# plant_long_life_v1_20.net
KiCad netlist of a schematic drawn in EAGLE
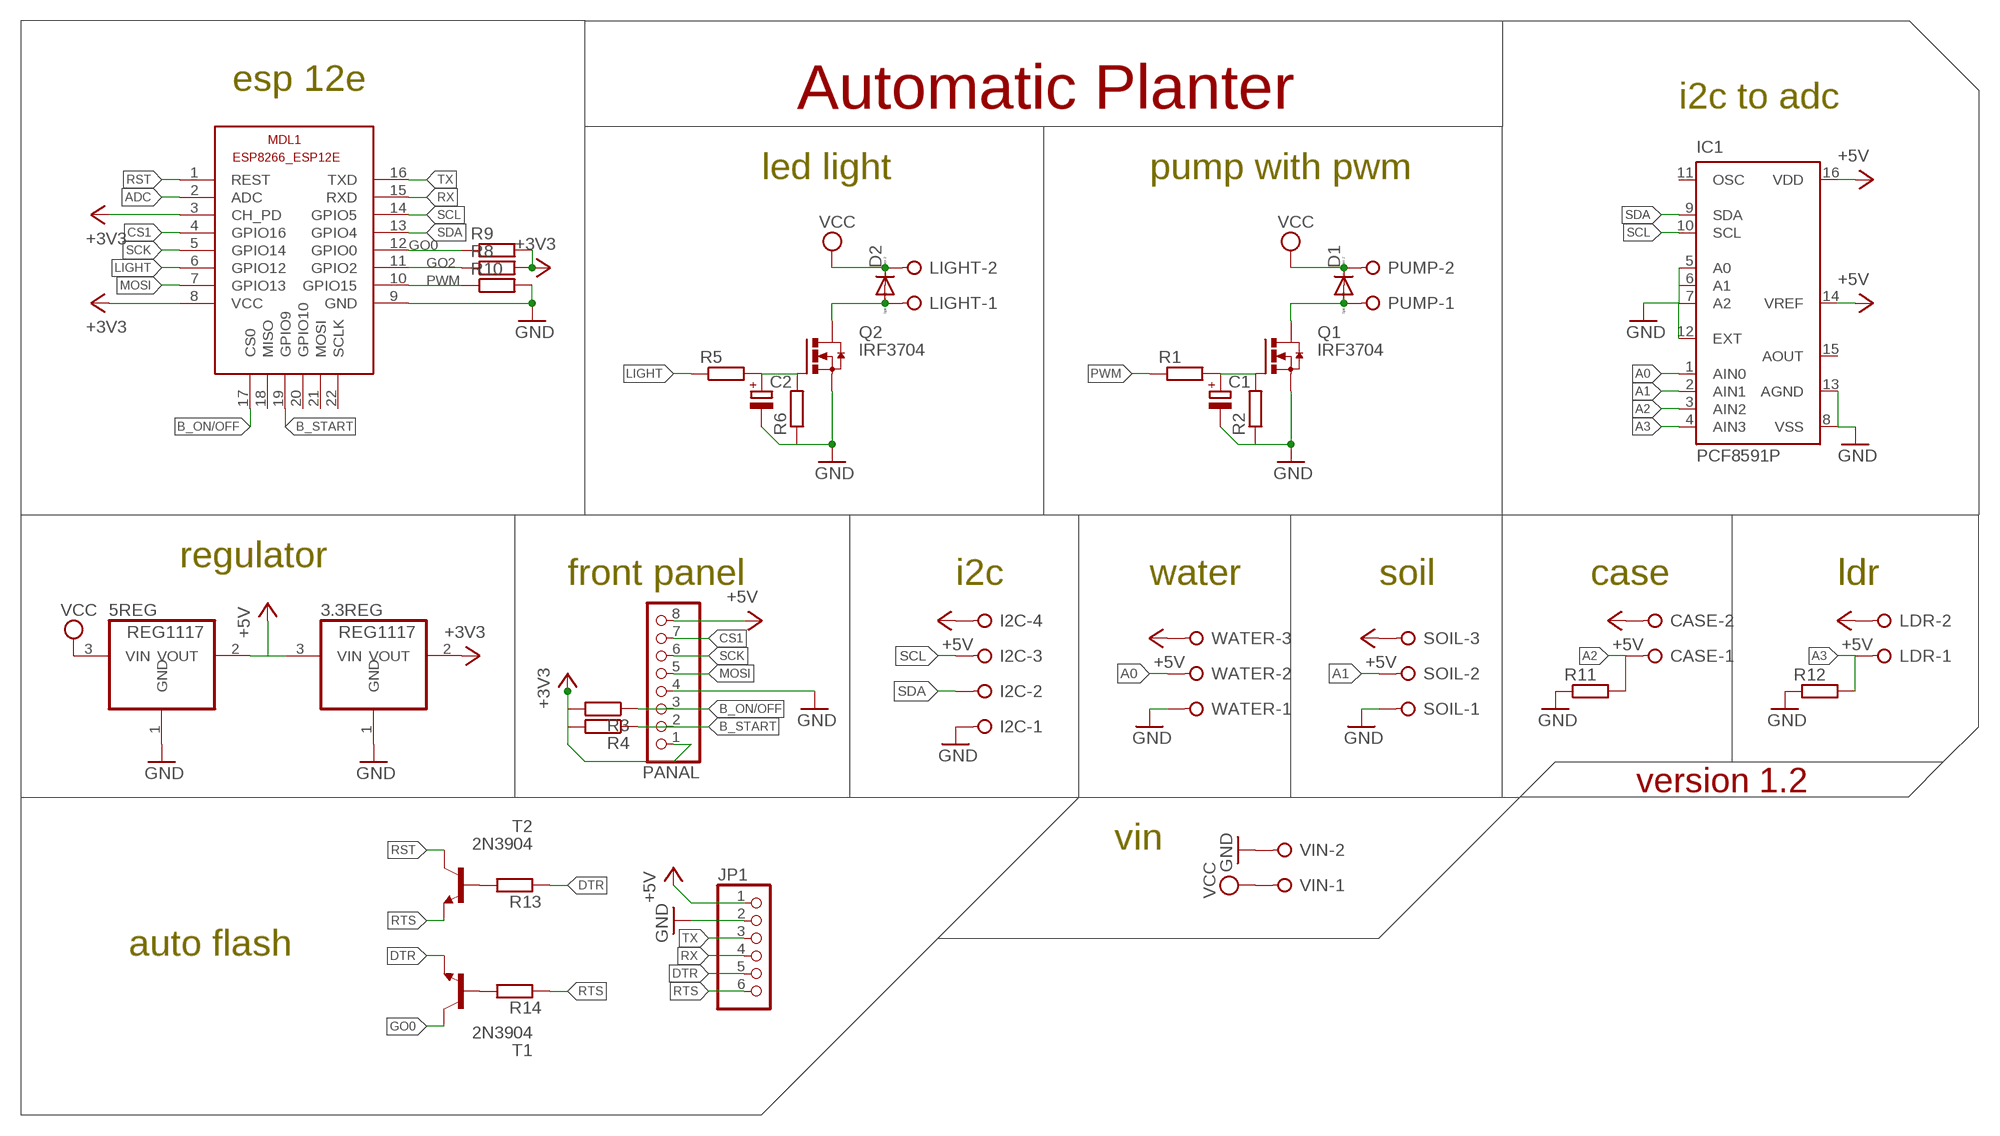
[diagram p0: schematic, sheet 1]

(export (version "E")
  (design (tool "Eeschema 10.0.6"))
  (components
    (comp (ref "3.3REG")
      (value "REG1117")
      (footprint "eagle-import:SOT223")
      (libsource (lib "eagle-import") (part "REG1117"))
    )
    (comp (ref "5REG")
      (value "REG1117")
      (footprint "eagle-import:SOT223")
      (libsource (lib "eagle-import") (part "REG1117"))
    )
    (comp (ref "C1")
      (value "CPOL-EUSMCA")
      (footprint "eagle-import:SMC_A")
      (libsource (lib "eagle-import") (part "CPOL-EUSMCA"))
    )
    (comp (ref "C2")
      (value "CPOL-EUSMCA")
      (footprint "eagle-import:SMC_A")
      (libsource (lib "eagle-import") (part "CPOL-EUSMCA"))
    )
    (comp (ref "CASE")
      (value "W237-02P")
      (footprint "eagle-import:W237-132")
      (libsource (lib "eagle-import") (part "W237-02P"))
    )
    (comp (ref "D1")
      (value "DIODE-DO214AA")
      (footprint "eagle-import:DO214AA")
      (libsource (lib "eagle-import") (part "DIODE-DO214AA"))
    )
    (comp (ref "D2")
      (value "DIODE-DO214AA")
      (footprint "eagle-import:DO214AA")
      (libsource (lib "eagle-import") (part "DIODE-DO214AA"))
    )
    (comp (ref "I2C")
      (value "W237-04P")
      (footprint "eagle-import:W237-4P")
      (libsource (lib "eagle-import") (part "W237-04P"))
    )
    (comp (ref "IC1")
      (value "PCF8591P")
      (footprint "eagle-import:DIL16")
      (fields (field (name "MF") "FARNELL"))
      (libsource (lib "eagle-import") (part "PCF8591P"))
    )
    (comp (ref "JP1")
      (value "PINHD-1X6")
      (footprint "eagle-import:1X06")
      (libsource (lib "eagle-import") (part "PINHD-1X6"))
    )
    (comp (ref "LDR")
      (value "W237-02P")
      (footprint "eagle-import:W237-132")
      (libsource (lib "eagle-import") (part "W237-02P"))
    )
    (comp (ref "LIGHT")
      (value "W237-02P")
      (footprint "eagle-import:W237-132")
      (libsource (lib "eagle-import") (part "W237-02P"))
    )
    (comp (ref "MDL1")
      (value "ESP8266-12EESP8266-ESP12E")
      (footprint "eagle-import:ESP8266-ESP12E")
      (libsource (lib "eagle-import") (part "ESP8266-12EESP8266-ESP12E"))
    )
    (comp (ref "PANAL")
      (value "PINHD-1X8")
      (footprint "eagle-import:1X08")
      (libsource (lib "eagle-import") (part "PINHD-1X8"))
    )
    (comp (ref "PUMP")
      (value "W237-02P")
      (footprint "eagle-import:W237-132")
      (libsource (lib "eagle-import") (part "W237-02P"))
    )
    (comp (ref "Q1")
      (value "IRF3704")
      (footprint "eagle-import:TO220AH")
      (libsource (lib "eagle-import") (part "IRF3704"))
    )
    (comp (ref "Q2")
      (value "IRF3704")
      (footprint "eagle-import:TO220AH")
      (libsource (lib "eagle-import") (part "IRF3704"))
    )
    (comp (ref "R1")
      (value "R-EU_R0805")
      (footprint "eagle-import:R0805")
      (libsource (lib "eagle-import") (part "R-EU_R0805"))
    )
    (comp (ref "R2")
      (value "R-EU_R0805")
      (footprint "eagle-import:R0805")
      (libsource (lib "eagle-import") (part "R-EU_R0805"))
    )
    (comp (ref "R3")
      (value "R-EU_R0805")
      (footprint "eagle-import:R0805")
      (libsource (lib "eagle-import") (part "R-EU_R0805"))
    )
    (comp (ref "R4")
      (value "R-EU_R0805")
      (footprint "eagle-import:R0805")
      (libsource (lib "eagle-import") (part "R-EU_R0805"))
    )
    (comp (ref "R5")
      (value "R-EU_R0805")
      (footprint "eagle-import:R0805")
      (libsource (lib "eagle-import") (part "R-EU_R0805"))
    )
    (comp (ref "R6")
      (value "R-EU_R0805")
      (footprint "eagle-import:R0805")
      (libsource (lib "eagle-import") (part "R-EU_R0805"))
    )
    (comp (ref "R8")
      (value "R-EU_R0603")
      (footprint "eagle-import:R0603")
      (libsource (lib "eagle-import") (part "R-EU_R0603"))
    )
    (comp (ref "R9")
      (value "R-EU_R0603")
      (footprint "eagle-import:R0603")
      (libsource (lib "eagle-import") (part "R-EU_R0603"))
    )
    (comp (ref "R10")
      (value "R-EU_R0603")
      (footprint "eagle-import:R0603")
      (libsource (lib "eagle-import") (part "R-EU_R0603"))
    )
    (comp (ref "R11")
      (value "R-EU_R0805")
      (footprint "eagle-import:R0805")
      (libsource (lib "eagle-import") (part "R-EU_R0805"))
    )
    (comp (ref "R12")
      (value "R-EU_R0805")
      (footprint "eagle-import:R0805")
      (libsource (lib "eagle-import") (part "R-EU_R0805"))
    )
    (comp (ref "R13")
      (value "R-EU_0204/7")
      (footprint "eagle-import:0204_7")
      (libsource (lib "eagle-import") (part "R-EU_0204/7"))
    )
    (comp (ref "R14")
      (value "R-EU_0204/7")
      (footprint "eagle-import:0204_7")
      (libsource (lib "eagle-import") (part "R-EU_0204/7"))
    )
    (comp (ref "SOIL")
      (value "W237-3E")
      (footprint "eagle-import:W237-3E")
      (libsource (lib "eagle-import") (part "W237-3E"))
    )
    (comp (ref "T1")
      (value "2N3904")
      (footprint "eagle-import:TO92")
      (libsource (lib "eagle-import") (part "2N3904"))
    )
    (comp (ref "T2")
      (value "2N3904")
      (footprint "eagle-import:TO92")
      (libsource (lib "eagle-import") (part "2N3904"))
    )
    (comp (ref "VIN")
      (value "W237-02P")
      (footprint "eagle-import:W237-132")
      (libsource (lib "eagle-import") (part "W237-02P"))
    )
    (comp (ref "WATER")
      (value "W237-3E")
      (footprint "eagle-import:W237-3E")
      (libsource (lib "eagle-import") (part "W237-3E"))
    )
  )
  (nets
    (net (code "1") (name "+3V3") (class "Default")
      (node (ref "3.3REG") (pin "2") (pinfunction "VOUT_2") (pintype "output"))
      (node (ref "MDL1") (pin "3") (pinfunction "CH_PD_3") (pintype "bidirectional"))
      (node (ref "MDL1") (pin "8") (pinfunction "VCC_8") (pintype "bidirectional"))
      (node (ref "PANAL") (pin "1") (pinfunction "1_1") (pintype "passive"))
      (node (ref "R3") (pin "2") (pinfunction "2_2") (pintype "passive"))
      (node (ref "R4") (pin "2") (pinfunction "2_2") (pintype "passive"))
      (node (ref "R8") (pin "2") (pinfunction "2_2") (pintype "passive"))
      (node (ref "R9") (pin "2") (pinfunction "2_2") (pintype "passive"))
    )
    (net (code "2") (name "+5V") (class "Default")
      (node (ref "3.3REG") (pin "3") (pinfunction "VIN_3") (pintype "input"))
      (node (ref "5REG") (pin "2") (pinfunction "VOUT_2") (pintype "output"))
      (node (ref "CASE") (pin "2") (pinfunction "KL_2") (pintype "passive"))
      (node (ref "I2C") (pin "4") (pinfunction "KL_4") (pintype "passive"))
      (node (ref "IC1") (pin "14") (pinfunction "VREF_14") (pintype "input"))
      (node (ref "IC1") (pin "16") (pinfunction "VDD_16") (pintype "power_in"))
      (node (ref "JP1") (pin "1") (pinfunction "1_1") (pintype "passive"))
      (node (ref "LDR") (pin "2") (pinfunction "KL_2") (pintype "passive"))
      (node (ref "PANAL") (pin "8") (pinfunction "8_8") (pintype "passive"))
      (node (ref "SOIL") (pin "3") (pinfunction "KL_3") (pintype "passive"))
      (node (ref "WATER") (pin "3") (pinfunction "KL_3") (pintype "passive"))
    )
    (net (code "3") (name "/GO2") (class "Default")
      (node (ref "MDL1") (pin "11") (pinfunction "GPIO2_11") (pintype "bidirectional"))
      (node (ref "R8") (pin "1") (pinfunction "1_1") (pintype "passive"))
    )
    (net (code "4") (name "A0") (class "Default")
      (node (ref "IC1") (pin "1") (pinfunction "AIN0_1") (pintype "input"))
      (node (ref "WATER") (pin "2") (pinfunction "KL_2") (pintype "passive"))
    )
    (net (code "5") (name "A1") (class "Default")
      (node (ref "IC1") (pin "2") (pinfunction "AIN1_2") (pintype "input"))
      (node (ref "SOIL") (pin "2") (pinfunction "KL_2") (pintype "passive"))
    )
    (net (code "6") (name "A2") (class "Default")
      (node (ref "CASE") (pin "1") (pinfunction "KL_1") (pintype "passive"))
      (node (ref "IC1") (pin "3") (pinfunction "AIN2_3") (pintype "input"))
      (node (ref "R11") (pin "2") (pinfunction "2_2") (pintype "passive"))
    )
    (net (code "7") (name "A3") (class "Default")
      (node (ref "IC1") (pin "4") (pinfunction "AIN3_4") (pintype "input"))
      (node (ref "LDR") (pin "1") (pinfunction "KL_1") (pintype "passive"))
      (node (ref "R12") (pin "2") (pinfunction "2_2") (pintype "passive"))
    )
    (net (code "8") (name "ADC") (class "Default")
      (node (ref "MDL1") (pin "2") (pinfunction "ADC_2") (pintype "bidirectional"))
    )
    (net (code "9") (name "B_ON{slash}OFF") (class "Default")
      (node (ref "MDL1") (pin "17") (pinfunction "CS0_17") (pintype "bidirectional"))
      (node (ref "PANAL") (pin "3") (pinfunction "3_3") (pintype "passive"))
      (node (ref "R3") (pin "1") (pinfunction "1_1") (pintype "passive"))
    )
    (net (code "10") (name "B_START") (class "Default")
      (node (ref "MDL1") (pin "19") (pinfunction "GPIO9_19") (pintype "bidirectional"))
      (node (ref "PANAL") (pin "2") (pinfunction "2_2") (pintype "passive"))
      (node (ref "R4") (pin "1") (pinfunction "1_1") (pintype "passive"))
    )
    (net (code "11") (name "CS1") (class "Default")
      (node (ref "MDL1") (pin "4") (pinfunction "GPIO16_4") (pintype "bidirectional"))
      (node (ref "PANAL") (pin "7") (pinfunction "7_7") (pintype "passive"))
    )
    (net (code "12") (name "DTR") (class "Default")
      (node (ref "JP1") (pin "5") (pinfunction "5_5") (pintype "passive"))
      (node (ref "R13") (pin "1") (pinfunction "1_1") (pintype "passive"))
      (node (ref "T1") (pin "3") (pinfunction "E_3") (pintype "passive"))
    )
    (net (code "13") (name "GND") (class "Default")
      (node (ref "3.3REG") (pin "1") (pinfunction "GND_1") (pintype "power_in"))
      (node (ref "5REG") (pin "1") (pinfunction "GND_1") (pintype "power_in"))
      (node (ref "C1") (pin "-") (pinfunction "-_-") (pintype "passive"))
      (node (ref "C2") (pin "-") (pinfunction "-_-") (pintype "passive"))
      (node (ref "I2C") (pin "1") (pinfunction "KL_1") (pintype "passive"))
      (node (ref "IC1") (pin "12") (pinfunction "EXT_12") (pintype "input"))
      (node (ref "IC1") (pin "13") (pinfunction "AGND_13") (pintype "power_in"))
      (node (ref "IC1") (pin "5") (pinfunction "A0_5") (pintype "input"))
      (node (ref "IC1") (pin "6") (pinfunction "A1_6") (pintype "input"))
      (node (ref "IC1") (pin "7") (pinfunction "A2_7") (pintype "input"))
      (node (ref "IC1") (pin "8") (pinfunction "VSS_8") (pintype "power_in"))
      (node (ref "JP1") (pin "2") (pinfunction "2_2") (pintype "passive"))
      (node (ref "MDL1") (pin "9") (pinfunction "GND_9") (pintype "bidirectional"))
      (node (ref "PANAL") (pin "4") (pinfunction "4_4") (pintype "passive"))
      (node (ref "Q1") (pin "E") (pinfunction "S_E") (pintype "passive"))
      (node (ref "Q2") (pin "E") (pinfunction "S_E") (pintype "passive"))
      (node (ref "R10") (pin "2") (pinfunction "2_2") (pintype "passive"))
      (node (ref "R11") (pin "1") (pinfunction "1_1") (pintype "passive"))
      (node (ref "R12") (pin "1") (pinfunction "1_1") (pintype "passive"))
      (node (ref "R2") (pin "1") (pinfunction "1_1") (pintype "passive"))
      (node (ref "R6") (pin "1") (pinfunction "1_1") (pintype "passive"))
      (node (ref "SOIL") (pin "1") (pinfunction "KL_1") (pintype "passive"))
      (node (ref "VIN") (pin "2") (pinfunction "KL_2") (pintype "passive"))
      (node (ref "WATER") (pin "1") (pinfunction "KL_1") (pintype "passive"))
    )
    (net (code "14") (name "GO0") (class "Default")
      (node (ref "MDL1") (pin "12") (pinfunction "GPIO0_12") (pintype "bidirectional"))
      (node (ref "R9") (pin "1") (pinfunction "1_1") (pintype "passive"))
      (node (ref "T1") (pin "1") (pinfunction "C_1") (pintype "passive"))
    )
    (net (code "15") (name "LIGHT") (class "Default")
      (node (ref "MDL1") (pin "6") (pinfunction "GPIO12_6") (pintype "bidirectional"))
      (node (ref "R5") (pin "1") (pinfunction "1_1") (pintype "passive"))
    )
    (net (code "16") (name "MOSI") (class "Default")
      (node (ref "MDL1") (pin "7") (pinfunction "GPIO13_7") (pintype "bidirectional"))
      (node (ref "PANAL") (pin "5") (pinfunction "5_5") (pintype "passive"))
    )
    (net (code "17") (name "Net-(LIGHTA-KL)") (class "Default")
      (node (ref "D2") (pin "A") (pinfunction "A_A") (pintype "passive"))
      (node (ref "LIGHT") (pin "1") (pinfunction "KL_1") (pintype "passive"))
      (node (ref "Q2") (pin "C") (pinfunction "D_C") (pintype "passive"))
    )
    (net (code "18") (name "Net-(PUMPA-KL)") (class "Default")
      (node (ref "D1") (pin "A") (pinfunction "A_A") (pintype "passive"))
      (node (ref "PUMP") (pin "1") (pinfunction "KL_1") (pintype "passive"))
      (node (ref "Q1") (pin "C") (pinfunction "D_C") (pintype "passive"))
    )
    (net (code "19") (name "Net-(Q1-G)") (class "Default")
      (node (ref "C1") (pin "+") (pinfunction "+_+") (pintype "passive"))
      (node (ref "Q1") (pin "B") (pinfunction "G_B") (pintype "passive"))
      (node (ref "R1") (pin "2") (pinfunction "2_2") (pintype "passive"))
      (node (ref "R2") (pin "2") (pinfunction "2_2") (pintype "passive"))
    )
    (net (code "20") (name "Net-(Q2-G)") (class "Default")
      (node (ref "C2") (pin "+") (pinfunction "+_+") (pintype "passive"))
      (node (ref "Q2") (pin "B") (pinfunction "G_B") (pintype "passive"))
      (node (ref "R5") (pin "2") (pinfunction "2_2") (pintype "passive"))
      (node (ref "R6") (pin "2") (pinfunction "2_2") (pintype "passive"))
    )
    (net (code "21") (name "Net-(T1-B)") (class "Default")
      (node (ref "R14") (pin "2") (pinfunction "2_2") (pintype "passive"))
      (node (ref "T1") (pin "2") (pinfunction "B_2") (pintype "passive"))
    )
    (net (code "22") (name "Net-(T2-B)") (class "Default")
      (node (ref "R13") (pin "2") (pinfunction "2_2") (pintype "passive"))
      (node (ref "T2") (pin "2") (pinfunction "B_2") (pintype "passive"))
    )
    (net (code "23") (name "PWM") (class "Default")
      (node (ref "MDL1") (pin "10") (pinfunction "GPIO15_10") (pintype "bidirectional"))
      (node (ref "R1") (pin "1") (pinfunction "1_1") (pintype "passive"))
      (node (ref "R10") (pin "1") (pinfunction "1_1") (pintype "passive"))
    )
    (net (code "24") (name "RST") (class "Default")
      (node (ref "MDL1") (pin "1") (pinfunction "REST_1") (pintype "bidirectional"))
      (node (ref "T2") (pin "1") (pinfunction "C_1") (pintype "passive"))
    )
    (net (code "25") (name "RTS") (class "Default")
      (node (ref "JP1") (pin "6") (pinfunction "6_6") (pintype "passive"))
      (node (ref "R14") (pin "1") (pinfunction "1_1") (pintype "passive"))
      (node (ref "T2") (pin "3") (pinfunction "E_3") (pintype "passive"))
    )
    (net (code "26") (name "RX") (class "Default")
      (node (ref "JP1") (pin "4") (pinfunction "4_4") (pintype "passive"))
      (node (ref "MDL1") (pin "15") (pinfunction "RXD_15") (pintype "bidirectional"))
    )
    (net (code "27") (name "SCK") (class "Default")
      (node (ref "MDL1") (pin "5") (pinfunction "GPIO14_5") (pintype "bidirectional"))
      (node (ref "PANAL") (pin "6") (pinfunction "6_6") (pintype "passive"))
    )
    (net (code "28") (name "SCL") (class "Default")
      (node (ref "I2C") (pin "3") (pinfunction "KL_3") (pintype "passive"))
      (node (ref "IC1") (pin "10") (pinfunction "SCL_10") (pintype "input"))
      (node (ref "MDL1") (pin "14") (pinfunction "GPIO5_14") (pintype "bidirectional"))
    )
    (net (code "29") (name "SDA") (class "Default")
      (node (ref "I2C") (pin "2") (pinfunction "KL_2") (pintype "passive"))
      (node (ref "IC1") (pin "9") (pinfunction "SDA_9") (pintype "bidirectional"))
      (node (ref "MDL1") (pin "13") (pinfunction "GPIO4_13") (pintype "bidirectional"))
    )
    (net (code "30") (name "TX") (class "Default")
      (node (ref "JP1") (pin "3") (pinfunction "3_3") (pintype "passive"))
      (node (ref "MDL1") (pin "16") (pinfunction "TXD_16") (pintype "bidirectional"))
    )
    (net (code "31") (name "VCC") (class "Default")
      (node (ref "5REG") (pin "3") (pinfunction "VIN_3") (pintype "input"))
      (node (ref "D1") (pin "C") (pinfunction "C_C") (pintype "passive"))
      (node (ref "D2") (pin "C") (pinfunction "C_C") (pintype "passive"))
      (node (ref "LIGHT") (pin "2") (pinfunction "KL_2") (pintype "passive"))
      (node (ref "PUMP") (pin "2") (pinfunction "KL_2") (pintype "passive"))
      (node (ref "VIN") (pin "1") (pinfunction "KL_1") (pintype "passive"))
    )
    (net (code "32") (name "unconnected-(IC1-AOUT-Pad15)") (class "Default")
      (node (ref "IC1") (pin "15") (pinfunction "AOUT_15") (pintype "output"))
    )
    (net (code "33") (name "unconnected-(IC1-OSC-Pad11)") (class "Default")
      (node (ref "IC1") (pin "11") (pinfunction "OSC_11") (pintype "input"))
    )
    (net (code "34") (name "unconnected-(MDL1-GPIO10-Pad20)") (class "Default")
      (node (ref "MDL1") (pin "20") (pinfunction "GPIO10_20") (pintype "bidirectional"))
    )
    (net (code "35") (name "unconnected-(MDL1-MISO-Pad18)") (class "Default")
      (node (ref "MDL1") (pin "18") (pinfunction "MISO_18") (pintype "bidirectional"))
    )
    (net (code "36") (name "unconnected-(MDL1-MOSI-Pad21)") (class "Default")
      (node (ref "MDL1") (pin "21") (pinfunction "MOSI_21") (pintype "bidirectional"))
    )
    (net (code "37") (name "unconnected-(MDL1-SCLK-Pad22)") (class "Default")
      (node (ref "MDL1") (pin "22") (pinfunction "SCLK_22") (pintype "bidirectional"))
    )
  )
)
